# StairLights_clips.net
KiCad netlist of a schematic drawn in EAGLE
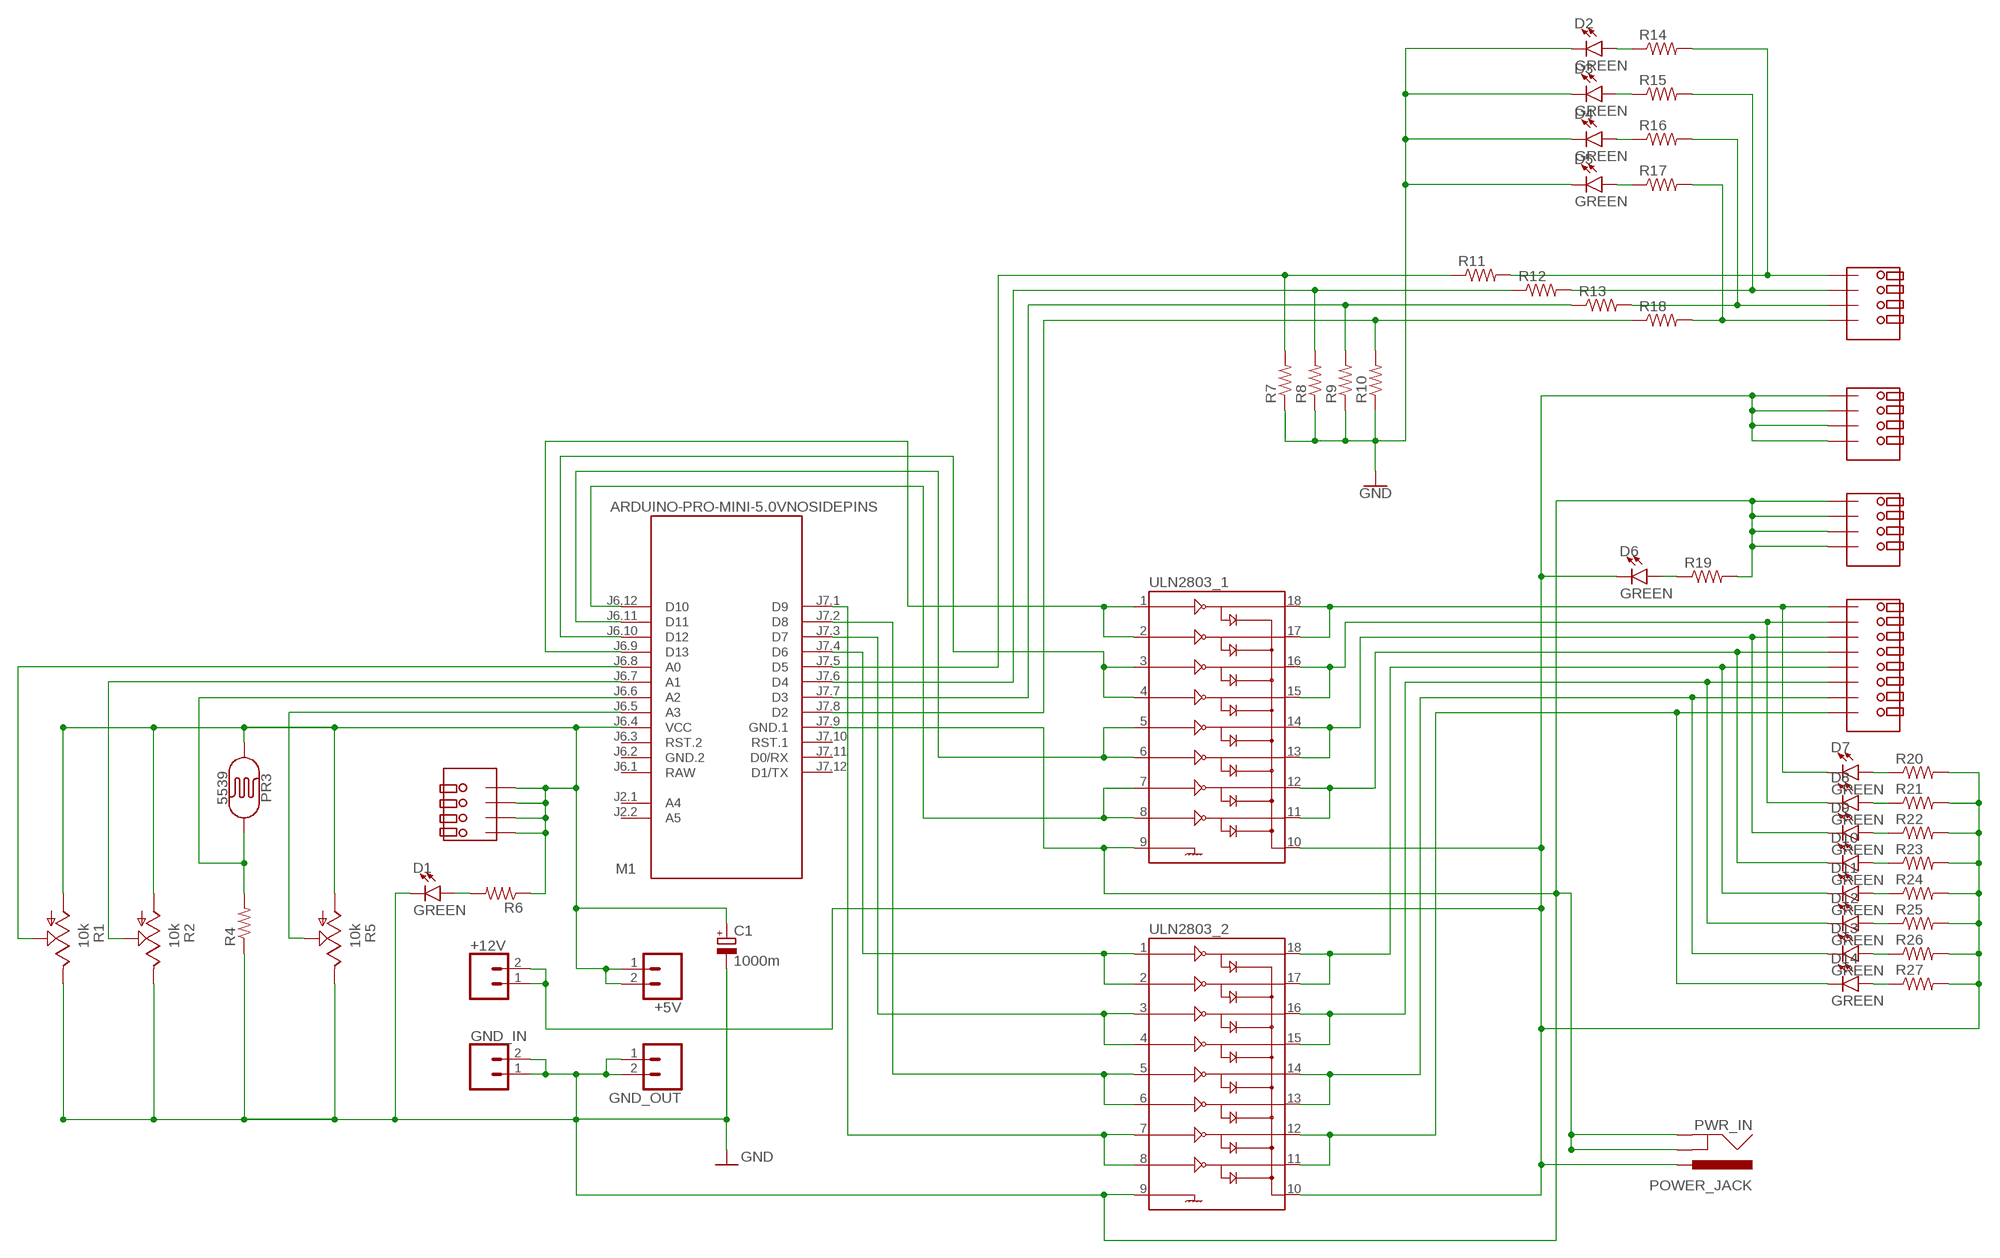
[diagram p0: schematic, sheet 1]

(export (version "E")
  (design (tool "Eeschema 10.0.6"))
  (components
    (comp (ref "+5V")
      (value "CONN_02")
      (footprint "eagle-import:1X02")
      (libsource (lib "eagle-import") (part "CONN_02"))
    )
    (comp (ref "+12V")
      (value "CONN_02")
      (footprint "eagle-import:1X02")
      (libsource (lib "eagle-import") (part "CONN_02"))
    )
    (comp (ref "C1")
      (value "1000m")
      (footprint "eagle-import:E5-5")
      (libsource (lib "eagle-import") (part "CPOL-EUE5-5"))
    )
    (comp (ref "D1")
      (value "GREEN")
      (footprint "eagle-import:LED-1206")
      (libsource (lib "eagle-import") (part "LED-GREEN1206"))
    )
    (comp (ref "D2")
      (value "GREEN")
      (footprint "eagle-import:LED-1206")
      (libsource (lib "eagle-import") (part "LED-GREEN1206"))
    )
    (comp (ref "D3")
      (value "GREEN")
      (footprint "eagle-import:LED-1206")
      (libsource (lib "eagle-import") (part "LED-GREEN1206"))
    )
    (comp (ref "D4")
      (value "GREEN")
      (footprint "eagle-import:LED-1206")
      (libsource (lib "eagle-import") (part "LED-GREEN1206"))
    )
    (comp (ref "D5")
      (value "GREEN")
      (footprint "eagle-import:LED-1206")
      (libsource (lib "eagle-import") (part "LED-GREEN1206"))
    )
    (comp (ref "D6")
      (value "GREEN")
      (footprint "eagle-import:LED-1206")
      (libsource (lib "eagle-import") (part "LED-GREEN1206"))
    )
    (comp (ref "D7")
      (value "GREEN")
      (footprint "eagle-import:LED-1206")
      (libsource (lib "eagle-import") (part "LED-GREEN1206"))
    )
    (comp (ref "D8")
      (value "GREEN")
      (footprint "eagle-import:LED-1206")
      (libsource (lib "eagle-import") (part "LED-GREEN1206"))
    )
    (comp (ref "D9")
      (value "GREEN")
      (footprint "eagle-import:LED-1206")
      (libsource (lib "eagle-import") (part "LED-GREEN1206"))
    )
    (comp (ref "D10")
      (value "GREEN")
      (footprint "eagle-import:LED-1206")
      (libsource (lib "eagle-import") (part "LED-GREEN1206"))
    )
    (comp (ref "D11")
      (value "GREEN")
      (footprint "eagle-import:LED-1206")
      (libsource (lib "eagle-import") (part "LED-GREEN1206"))
    )
    (comp (ref "D12")
      (value "GREEN")
      (footprint "eagle-import:LED-1206")
      (libsource (lib "eagle-import") (part "LED-GREEN1206"))
    )
    (comp (ref "D13")
      (value "GREEN")
      (footprint "eagle-import:LED-1206")
      (libsource (lib "eagle-import") (part "LED-GREEN1206"))
    )
    (comp (ref "D14")
      (value "GREEN")
      (footprint "eagle-import:LED-1206")
      (libsource (lib "eagle-import") (part "LED-GREEN1206"))
    )
    (comp (ref "GND_IN")
      (value "CONN_02")
      (footprint "eagle-import:1X02")
      (libsource (lib "eagle-import") (part "CONN_02"))
    )
    (comp (ref "GND_OUT")
      (value "CONN_02")
      (footprint "eagle-import:1X02")
      (libsource (lib "eagle-import") (part "CONN_02"))
    )
    (comp (ref "M1")
      (value "ARDUINO-PRO-MINI-5.0VNOSIDEPINS")
      (footprint "eagle-import:ARDUINO-PRO-MINI")
      (libsource (lib "eagle-import") (part "ARDUINO-PRO-MINI-NOSIDEPINS5.0V"))
    )
    (comp (ref "PR3")
      (value "5539")
      (footprint "eagle-import:PHOTOCELL")
      (libsource (lib "eagle-import") (part "PHOTOCELLPTH"))
    )
    (comp (ref "PWR_IN")
      (value "POWER_JACK")
      (footprint "eagle-import:POWER_JACK_PTH")
      (libsource (lib "eagle-import") (part "POWER_JACK"))
    )
    (comp (ref "R1")
      (value "10k")
      (footprint "eagle-import:S64W")
      (libsource (lib "eagle-import") (part "TRIM_US-S64W"))
    )
    (comp (ref "R2")
      (value "10k")
      (footprint "eagle-import:S64W")
      (libsource (lib "eagle-import") (part "TRIM_US-S64W"))
    )
    (comp (ref "R4")
      (value "10k")
      (footprint "eagle-import:R0805")
      (libsource (lib "eagle-import") (part "R-US_R0805"))
    )
    (comp (ref "R5")
      (value "10k")
      (footprint "eagle-import:S64W")
      (libsource (lib "eagle-import") (part "TRIM_US-S64W"))
    )
    (comp (ref "R6")
      (value "330")
      (footprint "eagle-import:R0805")
      (libsource (lib "eagle-import") (part "R-US_R0805"))
    )
    (comp (ref "R7")
      (value "10k")
      (footprint "eagle-import:R0805")
      (libsource (lib "eagle-import") (part "R-US_R0805"))
    )
    (comp (ref "R8")
      (value "10k")
      (footprint "eagle-import:R0805")
      (libsource (lib "eagle-import") (part "R-US_R0805"))
    )
    (comp (ref "R9")
      (value "10k")
      (footprint "eagle-import:R0805")
      (libsource (lib "eagle-import") (part "R-US_R0805"))
    )
    (comp (ref "R10")
      (value "10k")
      (footprint "eagle-import:R0805")
      (libsource (lib "eagle-import") (part "R-US_R0805"))
    )
    (comp (ref "R11")
      (value "330")
      (footprint "eagle-import:R0805")
      (libsource (lib "eagle-import") (part "R-US_R0805"))
    )
    (comp (ref "R12")
      (value "330")
      (footprint "eagle-import:R0805")
      (libsource (lib "eagle-import") (part "R-US_R0805"))
    )
    (comp (ref "R13")
      (value "330")
      (footprint "eagle-import:R0805")
      (libsource (lib "eagle-import") (part "R-US_R0805"))
    )
    (comp (ref "R14")
      (value "330")
      (footprint "eagle-import:R0805")
      (libsource (lib "eagle-import") (part "R-US_R0805"))
    )
    (comp (ref "R15")
      (value "330")
      (footprint "eagle-import:R0805")
      (libsource (lib "eagle-import") (part "R-US_R0805"))
    )
    (comp (ref "R16")
      (value "330")
      (footprint "eagle-import:R0805")
      (libsource (lib "eagle-import") (part "R-US_R0805"))
    )
    (comp (ref "R17")
      (value "330")
      (footprint "eagle-import:R0805")
      (libsource (lib "eagle-import") (part "R-US_R0805"))
    )
    (comp (ref "R18")
      (value "330")
      (footprint "eagle-import:R0805")
      (libsource (lib "eagle-import") (part "R-US_R0805"))
    )
    (comp (ref "R19")
      (value "330")
      (footprint "eagle-import:R0805")
      (libsource (lib "eagle-import") (part "R-US_R0805"))
    )
    (comp (ref "R20")
      (value "330")
      (footprint "eagle-import:R0805")
      (libsource (lib "eagle-import") (part "R-US_R0805"))
    )
    (comp (ref "R21")
      (value "330")
      (footprint "eagle-import:R0805")
      (libsource (lib "eagle-import") (part "R-US_R0805"))
    )
    (comp (ref "R22")
      (value "330")
      (footprint "eagle-import:R0805")
      (libsource (lib "eagle-import") (part "R-US_R0805"))
    )
    (comp (ref "R23")
      (value "330")
      (footprint "eagle-import:R0805")
      (libsource (lib "eagle-import") (part "R-US_R0805"))
    )
    (comp (ref "R24")
      (value "330")
      (footprint "eagle-import:R0805")
      (libsource (lib "eagle-import") (part "R-US_R0805"))
    )
    (comp (ref "R25")
      (value "330")
      (footprint "eagle-import:R0805")
      (libsource (lib "eagle-import") (part "R-US_R0805"))
    )
    (comp (ref "R26")
      (value "330")
      (footprint "eagle-import:R0805")
      (libsource (lib "eagle-import") (part "R-US_R0805"))
    )
    (comp (ref "R27")
      (value "330")
      (footprint "eagle-import:R0805")
      (libsource (lib "eagle-import") (part "R-US_R0805"))
    )
    (comp (ref "SC1")
      (value "KF141V-4")
      (footprint "eagle-import:KF141V-4")
      (libsource (lib "eagle-import") (part "KF141V-4"))
    )
    (comp (ref "SC2")
      (value "KF141V-4")
      (footprint "eagle-import:KF141V-4")
      (libsource (lib "eagle-import") (part "KF141V-4"))
    )
    (comp (ref "SC3")
      (value "KF141V-4")
      (footprint "eagle-import:KF141V-4")
      (libsource (lib "eagle-import") (part "KF141V-4"))
    )
    (comp (ref "SC4")
      (value "KF141V-4")
      (footprint "eagle-import:KF141V-4")
      (libsource (lib "eagle-import") (part "KF141V-4"))
    )
    (comp (ref "SC5")
      (value "KF141V-8")
      (footprint "eagle-import:KF141V-8")
      (libsource (lib "eagle-import") (part "KF141V-8"))
    )
    (comp (ref "ULN2803_1")
      (value "ULN2803DIP")
      (footprint "eagle-import:DIL18")
      (libsource (lib "eagle-import") (part "ULN2803DIP"))
    )
    (comp (ref "ULN2803_2")
      (value "ULN2803DIP")
      (footprint "eagle-import:DIL18")
      (libsource (lib "eagle-import") (part "ULN2803DIP"))
    )
  )
  (nets
    (net (code "1") (name "/GND.2") (class "Default")
      (node (ref "M1") (pin "J6.2") (pinfunction "GND.2_J6.2") (pintype "power_in"))
    )
    (net (code "2") (name "/RAW") (class "Default")
      (node (ref "M1") (pin "J6.1") (pinfunction "RAW_J6.1") (pintype "power_in"))
    )
    (net (code "3") (name "GND") (class "Default")
      (node (ref "C1") (pin "-") (pinfunction "-_-") (pintype "passive"))
      (node (ref "D1") (pin "C") (pinfunction "C_C") (pintype "passive"))
      (node (ref "D2") (pin "C") (pinfunction "C_C") (pintype "passive"))
      (node (ref "D3") (pin "C") (pinfunction "C_C") (pintype "passive"))
      (node (ref "D4") (pin "C") (pinfunction "C_C") (pintype "passive"))
      (node (ref "D5") (pin "C") (pinfunction "C_C") (pintype "passive"))
      (node (ref "GND_IN") (pin "1") (pinfunction "1_1") (pintype "passive"))
      (node (ref "GND_IN") (pin "2") (pinfunction "2_2") (pintype "passive"))
      (node (ref "GND_OUT") (pin "1") (pinfunction "1_1") (pintype "passive"))
      (node (ref "GND_OUT") (pin "2") (pinfunction "2_2") (pintype "passive"))
      (node (ref "M1") (pin "J7.9") (pinfunction "GND.1_J7.9") (pintype "power_in"))
      (node (ref "PWR_IN") (pin "GND") (pinfunction "GND_GND") (pintype "bidirectional"))
      (node (ref "PWR_IN") (pin "GNDBREAK") (pinfunction "GNDBREAK_GNDBREAK") (pintype "bidirectional"))
      (node (ref "R1") (pin "E") (pinfunction "E_E") (pintype "passive"))
      (node (ref "R10") (pin "1") (pinfunction "1_1") (pintype "passive"))
      (node (ref "R19") (pin "2") (pinfunction "2_2") (pintype "passive"))
      (node (ref "R2") (pin "E") (pinfunction "E_E") (pintype "passive"))
      (node (ref "R4") (pin "1") (pinfunction "1_1") (pintype "passive"))
      (node (ref "R5") (pin "E") (pinfunction "E_E") (pintype "passive"))
      (node (ref "R7") (pin "1") (pinfunction "1_1") (pintype "passive"))
      (node (ref "R8") (pin "1") (pinfunction "1_1") (pintype "passive"))
      (node (ref "R9") (pin "1") (pinfunction "1_1") (pintype "passive"))
      (node (ref "SC4") (pin "P$1") (pinfunction "P$1_P$1") (pintype "bidirectional"))
      (node (ref "SC4") (pin "P$10") (pinfunction "P$2_P$10") (pintype "bidirectional"))
      (node (ref "SC4") (pin "P$11") (pinfunction "P$3_P$11") (pintype "bidirectional"))
      (node (ref "SC4") (pin "P$12") (pinfunction "P$4_P$12") (pintype "bidirectional"))
      (node (ref "SC4") (pin "P$2") (pinfunction "P$2_P$2") (pintype "bidirectional"))
      (node (ref "SC4") (pin "P$3") (pinfunction "P$3_P$3") (pintype "bidirectional"))
      (node (ref "SC4") (pin "P$4") (pinfunction "P$4_P$4") (pintype "bidirectional"))
      (node (ref "SC4") (pin "P$9") (pinfunction "P$1_P$9") (pintype "bidirectional"))
      (node (ref "ULN2803_1") (pin "9") (pinfunction "9_9") (pintype "bidirectional"))
      (node (ref "ULN2803_2") (pin "9") (pinfunction "9_9") (pintype "bidirectional"))
    )
    (net (code "4") (name "Net-(+12V-Pad1)") (class "Default")
      (node (ref "+12V") (pin "1") (pinfunction "1_1") (pintype "passive"))
      (node (ref "+12V") (pin "2") (pinfunction "2_2") (pintype "passive"))
      (node (ref "D6") (pin "C") (pinfunction "C_C") (pintype "passive"))
      (node (ref "PWR_IN") (pin "PWR") (pinfunction "PWR_PWR") (pintype "bidirectional"))
      (node (ref "R20") (pin "2") (pinfunction "2_2") (pintype "passive"))
      (node (ref "R21") (pin "2") (pinfunction "2_2") (pintype "passive"))
      (node (ref "R22") (pin "2") (pinfunction "2_2") (pintype "passive"))
      (node (ref "R23") (pin "2") (pinfunction "2_2") (pintype "passive"))
      (node (ref "R24") (pin "2") (pinfunction "2_2") (pintype "passive"))
      (node (ref "R25") (pin "2") (pinfunction "2_2") (pintype "passive"))
      (node (ref "R26") (pin "2") (pinfunction "2_2") (pintype "passive"))
      (node (ref "R27") (pin "2") (pinfunction "2_2") (pintype "passive"))
      (node (ref "SC3") (pin "P$1") (pinfunction "P$1_P$1") (pintype "bidirectional"))
      (node (ref "SC3") (pin "P$10") (pinfunction "P$2_P$10") (pintype "bidirectional"))
      (node (ref "SC3") (pin "P$11") (pinfunction "P$3_P$11") (pintype "bidirectional"))
      (node (ref "SC3") (pin "P$12") (pinfunction "P$4_P$12") (pintype "bidirectional"))
      (node (ref "SC3") (pin "P$2") (pinfunction "P$2_P$2") (pintype "bidirectional"))
      (node (ref "SC3") (pin "P$3") (pinfunction "P$3_P$3") (pintype "bidirectional"))
      (node (ref "SC3") (pin "P$4") (pinfunction "P$4_P$4") (pintype "bidirectional"))
      (node (ref "SC3") (pin "P$9") (pinfunction "P$1_P$9") (pintype "bidirectional"))
      (node (ref "ULN2803_1") (pin "10") (pinfunction "10_10") (pintype "bidirectional"))
      (node (ref "ULN2803_2") (pin "10") (pinfunction "10_10") (pintype "bidirectional"))
    )
    (net (code "5") (name "Net-(D1-PadA)") (class "Default")
      (node (ref "D1") (pin "A") (pinfunction "A_A") (pintype "passive"))
      (node (ref "R6") (pin "2") (pinfunction "2_2") (pintype "passive"))
    )
    (net (code "6") (name "Net-(D2-PadA)") (class "Default")
      (node (ref "D2") (pin "A") (pinfunction "A_A") (pintype "passive"))
      (node (ref "R14") (pin "1") (pinfunction "1_1") (pintype "passive"))
    )
    (net (code "7") (name "Net-(D3-PadA)") (class "Default")
      (node (ref "D3") (pin "A") (pinfunction "A_A") (pintype "passive"))
      (node (ref "R15") (pin "1") (pinfunction "1_1") (pintype "passive"))
    )
    (net (code "8") (name "Net-(D4-PadA)") (class "Default")
      (node (ref "D4") (pin "A") (pinfunction "A_A") (pintype "passive"))
      (node (ref "R16") (pin "1") (pinfunction "1_1") (pintype "passive"))
    )
    (net (code "9") (name "Net-(D5-PadA)") (class "Default")
      (node (ref "D5") (pin "A") (pinfunction "A_A") (pintype "passive"))
      (node (ref "R17") (pin "1") (pinfunction "1_1") (pintype "passive"))
    )
    (net (code "10") (name "Net-(D6-PadA)") (class "Default")
      (node (ref "D6") (pin "A") (pinfunction "A_A") (pintype "passive"))
      (node (ref "R19") (pin "1") (pinfunction "1_1") (pintype "passive"))
    )
    (net (code "11") (name "Net-(D7-PadA)") (class "Default")
      (node (ref "D7") (pin "A") (pinfunction "A_A") (pintype "passive"))
      (node (ref "R20") (pin "1") (pinfunction "1_1") (pintype "passive"))
    )
    (net (code "12") (name "Net-(D7-PadC)") (class "Default")
      (node (ref "D7") (pin "C") (pinfunction "C_C") (pintype "passive"))
      (node (ref "SC5") (pin "P$1") (pinfunction "P$1_P$1") (pintype "bidirectional"))
      (node (ref "SC5") (pin "P$9") (pinfunction "P$1_P$9") (pintype "bidirectional"))
      (node (ref "ULN2803_1") (pin "17") (pinfunction "17_17") (pintype "bidirectional"))
      (node (ref "ULN2803_1") (pin "18") (pinfunction "18_18") (pintype "bidirectional"))
    )
    (net (code "13") (name "Net-(D8-PadA)") (class "Default")
      (node (ref "D8") (pin "A") (pinfunction "A_A") (pintype "passive"))
      (node (ref "R21") (pin "1") (pinfunction "1_1") (pintype "passive"))
    )
    (net (code "14") (name "Net-(D8-PadC)") (class "Default")
      (node (ref "D8") (pin "C") (pinfunction "C_C") (pintype "passive"))
      (node (ref "SC5") (pin "P$10") (pinfunction "P$2_P$10") (pintype "bidirectional"))
      (node (ref "SC5") (pin "P$2") (pinfunction "P$2_P$2") (pintype "bidirectional"))
      (node (ref "ULN2803_1") (pin "15") (pinfunction "15_15") (pintype "bidirectional"))
      (node (ref "ULN2803_1") (pin "16") (pinfunction "16_16") (pintype "bidirectional"))
    )
    (net (code "15") (name "Net-(D9-PadA)") (class "Default")
      (node (ref "D9") (pin "A") (pinfunction "A_A") (pintype "passive"))
      (node (ref "R22") (pin "1") (pinfunction "1_1") (pintype "passive"))
    )
    (net (code "16") (name "Net-(D9-PadC)") (class "Default")
      (node (ref "D9") (pin "C") (pinfunction "C_C") (pintype "passive"))
      (node (ref "SC5") (pin "P$11") (pinfunction "P$3_P$11") (pintype "bidirectional"))
      (node (ref "SC5") (pin "P$3") (pinfunction "P$3_P$3") (pintype "bidirectional"))
      (node (ref "ULN2803_1") (pin "13") (pinfunction "13_13") (pintype "bidirectional"))
      (node (ref "ULN2803_1") (pin "14") (pinfunction "14_14") (pintype "bidirectional"))
    )
    (net (code "17") (name "Net-(D10-PadA)") (class "Default")
      (node (ref "D10") (pin "A") (pinfunction "A_A") (pintype "passive"))
      (node (ref "R23") (pin "1") (pinfunction "1_1") (pintype "passive"))
    )
    (net (code "18") (name "Net-(D10-PadC)") (class "Default")
      (node (ref "D10") (pin "C") (pinfunction "C_C") (pintype "passive"))
      (node (ref "SC5") (pin "P$12") (pinfunction "P$4_P$12") (pintype "bidirectional"))
      (node (ref "SC5") (pin "P$4") (pinfunction "P$4_P$4") (pintype "bidirectional"))
      (node (ref "ULN2803_1") (pin "11") (pinfunction "11_11") (pintype "bidirectional"))
      (node (ref "ULN2803_1") (pin "12") (pinfunction "12_12") (pintype "bidirectional"))
    )
    (net (code "19") (name "Net-(D11-PadA)") (class "Default")
      (node (ref "D11") (pin "A") (pinfunction "A_A") (pintype "passive"))
      (node (ref "R24") (pin "1") (pinfunction "1_1") (pintype "passive"))
    )
    (net (code "20") (name "Net-(D11-PadC)") (class "Default")
      (node (ref "D11") (pin "C") (pinfunction "C_C") (pintype "passive"))
      (node (ref "SC5") (pin "P$13") (pinfunction "P$5_P$13") (pintype "bidirectional"))
      (node (ref "SC5") (pin "P$5") (pinfunction "P$5_P$5") (pintype "bidirectional"))
      (node (ref "ULN2803_2") (pin "17") (pinfunction "17_17") (pintype "bidirectional"))
      (node (ref "ULN2803_2") (pin "18") (pinfunction "18_18") (pintype "bidirectional"))
    )
    (net (code "21") (name "Net-(D12-PadA)") (class "Default")
      (node (ref "D12") (pin "A") (pinfunction "A_A") (pintype "passive"))
      (node (ref "R25") (pin "1") (pinfunction "1_1") (pintype "passive"))
    )
    (net (code "22") (name "Net-(D12-PadC)") (class "Default")
      (node (ref "D12") (pin "C") (pinfunction "C_C") (pintype "passive"))
      (node (ref "SC5") (pin "P$14") (pinfunction "P$6_P$14") (pintype "bidirectional"))
      (node (ref "SC5") (pin "P$6") (pinfunction "P$6_P$6") (pintype "bidirectional"))
      (node (ref "ULN2803_2") (pin "15") (pinfunction "15_15") (pintype "bidirectional"))
      (node (ref "ULN2803_2") (pin "16") (pinfunction "16_16") (pintype "bidirectional"))
    )
    (net (code "23") (name "Net-(D13-PadA)") (class "Default")
      (node (ref "D13") (pin "A") (pinfunction "A_A") (pintype "passive"))
      (node (ref "R26") (pin "1") (pinfunction "1_1") (pintype "passive"))
    )
    (net (code "24") (name "Net-(D13-PadC)") (class "Default")
      (node (ref "D13") (pin "C") (pinfunction "C_C") (pintype "passive"))
      (node (ref "SC5") (pin "P$15") (pinfunction "P$7_P$15") (pintype "bidirectional"))
      (node (ref "SC5") (pin "P$7") (pinfunction "P$7_P$7") (pintype "bidirectional"))
      (node (ref "ULN2803_2") (pin "13") (pinfunction "13_13") (pintype "bidirectional"))
      (node (ref "ULN2803_2") (pin "14") (pinfunction "14_14") (pintype "bidirectional"))
    )
    (net (code "25") (name "Net-(D14-PadA)") (class "Default")
      (node (ref "D14") (pin "A") (pinfunction "A_A") (pintype "passive"))
      (node (ref "R27") (pin "1") (pinfunction "1_1") (pintype "passive"))
    )
    (net (code "26") (name "Net-(D14-PadC)") (class "Default")
      (node (ref "D14") (pin "C") (pinfunction "C_C") (pintype "passive"))
      (node (ref "SC5") (pin "P$16") (pinfunction "P$8_P$16") (pintype "bidirectional"))
      (node (ref "SC5") (pin "P$8") (pinfunction "P$8_P$8") (pintype "bidirectional"))
      (node (ref "ULN2803_2") (pin "11") (pinfunction "11_11") (pintype "bidirectional"))
      (node (ref "ULN2803_2") (pin "12") (pinfunction "12_12") (pintype "bidirectional"))
    )
    (net (code "27") (name "Net-(M1-A0)") (class "Default")
      (node (ref "M1") (pin "J6.8") (pinfunction "A0_J6.8") (pintype "bidirectional"))
      (node (ref "R1") (pin "S") (pinfunction "S_S") (pintype "passive"))
    )
    (net (code "28") (name "Net-(M1-A1)") (class "Default")
      (node (ref "M1") (pin "J6.7") (pinfunction "A1_J6.7") (pintype "bidirectional"))
      (node (ref "R2") (pin "S") (pinfunction "S_S") (pintype "passive"))
    )
    (net (code "29") (name "Net-(M1-A2)") (class "Default")
      (node (ref "M1") (pin "J6.6") (pinfunction "A2_J6.6") (pintype "bidirectional"))
      (node (ref "PR3") (pin "2") (pinfunction "P$2_2") (pintype "bidirectional"))
      (node (ref "R4") (pin "2") (pinfunction "2_2") (pintype "passive"))
    )
    (net (code "30") (name "Net-(M1-A3)") (class "Default")
      (node (ref "M1") (pin "J6.5") (pinfunction "A3_J6.5") (pintype "bidirectional"))
      (node (ref "R5") (pin "S") (pinfunction "S_S") (pintype "passive"))
    )
    (net (code "31") (name "Net-(M1-D2)") (class "Default")
      (node (ref "M1") (pin "J7.8") (pinfunction "D2_J7.8") (pintype "bidirectional"))
      (node (ref "R10") (pin "2") (pinfunction "2_2") (pintype "passive"))
      (node (ref "R18") (pin "1") (pinfunction "1_1") (pintype "passive"))
    )
    (net (code "32") (name "Net-(M1-D3)") (class "Default")
      (node (ref "M1") (pin "J7.7") (pinfunction "D3_J7.7") (pintype "bidirectional"))
      (node (ref "R13") (pin "1") (pinfunction "1_1") (pintype "passive"))
      (node (ref "R9") (pin "2") (pinfunction "2_2") (pintype "passive"))
    )
    (net (code "33") (name "Net-(M1-D4)") (class "Default")
      (node (ref "M1") (pin "J7.6") (pinfunction "D4_J7.6") (pintype "bidirectional"))
      (node (ref "R12") (pin "1") (pinfunction "1_1") (pintype "passive"))
      (node (ref "R8") (pin "2") (pinfunction "2_2") (pintype "passive"))
    )
    (net (code "34") (name "Net-(M1-D5)") (class "Default")
      (node (ref "M1") (pin "J7.5") (pinfunction "D5_J7.5") (pintype "bidirectional"))
      (node (ref "R11") (pin "1") (pinfunction "1_1") (pintype "passive"))
      (node (ref "R7") (pin "2") (pinfunction "2_2") (pintype "passive"))
    )
    (net (code "35") (name "Net-(M1-D6)") (class "Default")
      (node (ref "M1") (pin "J7.4") (pinfunction "D6_J7.4") (pintype "bidirectional"))
      (node (ref "ULN2803_2") (pin "1") (pinfunction "1_1") (pintype "bidirectional"))
      (node (ref "ULN2803_2") (pin "2") (pinfunction "2_2") (pintype "bidirectional"))
    )
    (net (code "36") (name "Net-(M1-D7)") (class "Default")
      (node (ref "M1") (pin "J7.3") (pinfunction "D7_J7.3") (pintype "bidirectional"))
      (node (ref "ULN2803_2") (pin "3") (pinfunction "3_3") (pintype "bidirectional"))
      (node (ref "ULN2803_2") (pin "4") (pinfunction "4_4") (pintype "bidirectional"))
    )
    (net (code "37") (name "Net-(M1-D8)") (class "Default")
      (node (ref "M1") (pin "J7.2") (pinfunction "D8_J7.2") (pintype "bidirectional"))
      (node (ref "ULN2803_2") (pin "5") (pinfunction "5_5") (pintype "bidirectional"))
      (node (ref "ULN2803_2") (pin "6") (pinfunction "6_6") (pintype "bidirectional"))
    )
    (net (code "38") (name "Net-(M1-D9)") (class "Default")
      (node (ref "M1") (pin "J7.1") (pinfunction "D9_J7.1") (pintype "bidirectional"))
      (node (ref "ULN2803_2") (pin "7") (pinfunction "7_7") (pintype "bidirectional"))
      (node (ref "ULN2803_2") (pin "8") (pinfunction "8_8") (pintype "bidirectional"))
    )
    (net (code "39") (name "Net-(M1-D10)") (class "Default")
      (node (ref "M1") (pin "J6.12") (pinfunction "D10_J6.12") (pintype "bidirectional"))
      (node (ref "ULN2803_1") (pin "7") (pinfunction "7_7") (pintype "bidirectional"))
      (node (ref "ULN2803_1") (pin "8") (pinfunction "8_8") (pintype "bidirectional"))
    )
    (net (code "40") (name "Net-(M1-D11)") (class "Default")
      (node (ref "M1") (pin "J6.11") (pinfunction "D11_J6.11") (pintype "bidirectional"))
      (node (ref "ULN2803_1") (pin "5") (pinfunction "5_5") (pintype "bidirectional"))
      (node (ref "ULN2803_1") (pin "6") (pinfunction "6_6") (pintype "bidirectional"))
    )
    (net (code "41") (name "Net-(M1-D12)") (class "Default")
      (node (ref "M1") (pin "J6.10") (pinfunction "D12_J6.10") (pintype "bidirectional"))
      (node (ref "ULN2803_1") (pin "3") (pinfunction "3_3") (pintype "bidirectional"))
      (node (ref "ULN2803_1") (pin "4") (pinfunction "4_4") (pintype "bidirectional"))
    )
    (net (code "42") (name "Net-(M1-D13)") (class "Default")
      (node (ref "M1") (pin "J6.9") (pinfunction "D13_J6.9") (pintype "bidirectional"))
      (node (ref "ULN2803_1") (pin "1") (pinfunction "1_1") (pintype "bidirectional"))
      (node (ref "ULN2803_1") (pin "2") (pinfunction "2_2") (pintype "bidirectional"))
    )
    (net (code "43") (name "Net-(M1-VCC)") (class "Default")
      (node (ref "+5V") (pin "1") (pinfunction "1_1") (pintype "passive"))
      (node (ref "+5V") (pin "2") (pinfunction "2_2") (pintype "passive"))
      (node (ref "C1") (pin "+") (pinfunction "+_+") (pintype "passive"))
      (node (ref "M1") (pin "J6.4") (pinfunction "VCC_J6.4") (pintype "power_in"))
      (node (ref "PR3") (pin "1") (pinfunction "P$1_1") (pintype "bidirectional"))
      (node (ref "R1") (pin "A") (pinfunction "A_A") (pintype "passive"))
      (node (ref "R2") (pin "A") (pinfunction "A_A") (pintype "passive"))
      (node (ref "R5") (pin "A") (pinfunction "A_A") (pintype "passive"))
      (node (ref "R6") (pin "1") (pinfunction "1_1") (pintype "passive"))
      (node (ref "SC1") (pin "P$1") (pinfunction "P$1_P$1") (pintype "bidirectional"))
      (node (ref "SC1") (pin "P$10") (pinfunction "P$2_P$10") (pintype "bidirectional"))
      (node (ref "SC1") (pin "P$11") (pinfunction "P$3_P$11") (pintype "bidirectional"))
      (node (ref "SC1") (pin "P$12") (pinfunction "P$4_P$12") (pintype "bidirectional"))
      (node (ref "SC1") (pin "P$2") (pinfunction "P$2_P$2") (pintype "bidirectional"))
      (node (ref "SC1") (pin "P$3") (pinfunction "P$3_P$3") (pintype "bidirectional"))
      (node (ref "SC1") (pin "P$4") (pinfunction "P$4_P$4") (pintype "bidirectional"))
      (node (ref "SC1") (pin "P$9") (pinfunction "P$1_P$9") (pintype "bidirectional"))
    )
    (net (code "44") (name "Net-(R11-Pad2)") (class "Default")
      (node (ref "R11") (pin "2") (pinfunction "2_2") (pintype "passive"))
      (node (ref "R14") (pin "2") (pinfunction "2_2") (pintype "passive"))
      (node (ref "SC2") (pin "P$1") (pinfunction "P$1_P$1") (pintype "bidirectional"))
      (node (ref "SC2") (pin "P$9") (pinfunction "P$1_P$9") (pintype "bidirectional"))
    )
    (net (code "45") (name "Net-(R12-Pad2)") (class "Default")
      (node (ref "R12") (pin "2") (pinfunction "2_2") (pintype "passive"))
      (node (ref "R15") (pin "2") (pinfunction "2_2") (pintype "passive"))
      (node (ref "SC2") (pin "P$10") (pinfunction "P$2_P$10") (pintype "bidirectional"))
      (node (ref "SC2") (pin "P$2") (pinfunction "P$2_P$2") (pintype "bidirectional"))
    )
    (net (code "46") (name "Net-(R13-Pad2)") (class "Default")
      (node (ref "R13") (pin "2") (pinfunction "2_2") (pintype "passive"))
      (node (ref "R16") (pin "2") (pinfunction "2_2") (pintype "passive"))
      (node (ref "SC2") (pin "P$11") (pinfunction "P$3_P$11") (pintype "bidirectional"))
      (node (ref "SC2") (pin "P$3") (pinfunction "P$3_P$3") (pintype "bidirectional"))
    )
    (net (code "47") (name "Net-(R17-Pad2)") (class "Default")
      (node (ref "R17") (pin "2") (pinfunction "2_2") (pintype "passive"))
      (node (ref "R18") (pin "2") (pinfunction "2_2") (pintype "passive"))
      (node (ref "SC2") (pin "P$12") (pinfunction "P$4_P$12") (pintype "bidirectional"))
      (node (ref "SC2") (pin "P$4") (pinfunction "P$4_P$4") (pintype "bidirectional"))
    )
    (net (code "48") (name "unconnected-(M1-A4-PadJ2.1)") (class "Default")
      (node (ref "M1") (pin "J2.1") (pinfunction "A4_J2.1") (pintype "bidirectional"))
    )
    (net (code "49") (name "unconnected-(M1-A5-PadJ2.2)") (class "Default")
      (node (ref "M1") (pin "J2.2") (pinfunction "A5_J2.2") (pintype "bidirectional"))
    )
    (net (code "50") (name "unconnected-(M1-D0{slash}RX-PadJ7.11)") (class "Default")
      (node (ref "M1") (pin "J7.11") (pinfunction "D0/RX_J7.11") (pintype "bidirectional"))
    )
    (net (code "51") (name "unconnected-(M1-D1{slash}TX-PadJ7.12)") (class "Default")
      (node (ref "M1") (pin "J7.12") (pinfunction "D1/TX_J7.12") (pintype "bidirectional"))
    )
    (net (code "52") (name "unconnected-(M1-RST.1-PadJ7.10)") (class "Default")
      (node (ref "M1") (pin "J7.10") (pinfunction "RST.1_J7.10") (pintype "bidirectional"))
    )
    (net (code "53") (name "unconnected-(M1-RST.2-PadJ6.3)") (class "Default")
      (node (ref "M1") (pin "J6.3") (pinfunction "RST.2_J6.3") (pintype "bidirectional"))
    )
  )
)
